# DifferentialPair.net
KiCad netlist of a schematic drawn in Altium Designer
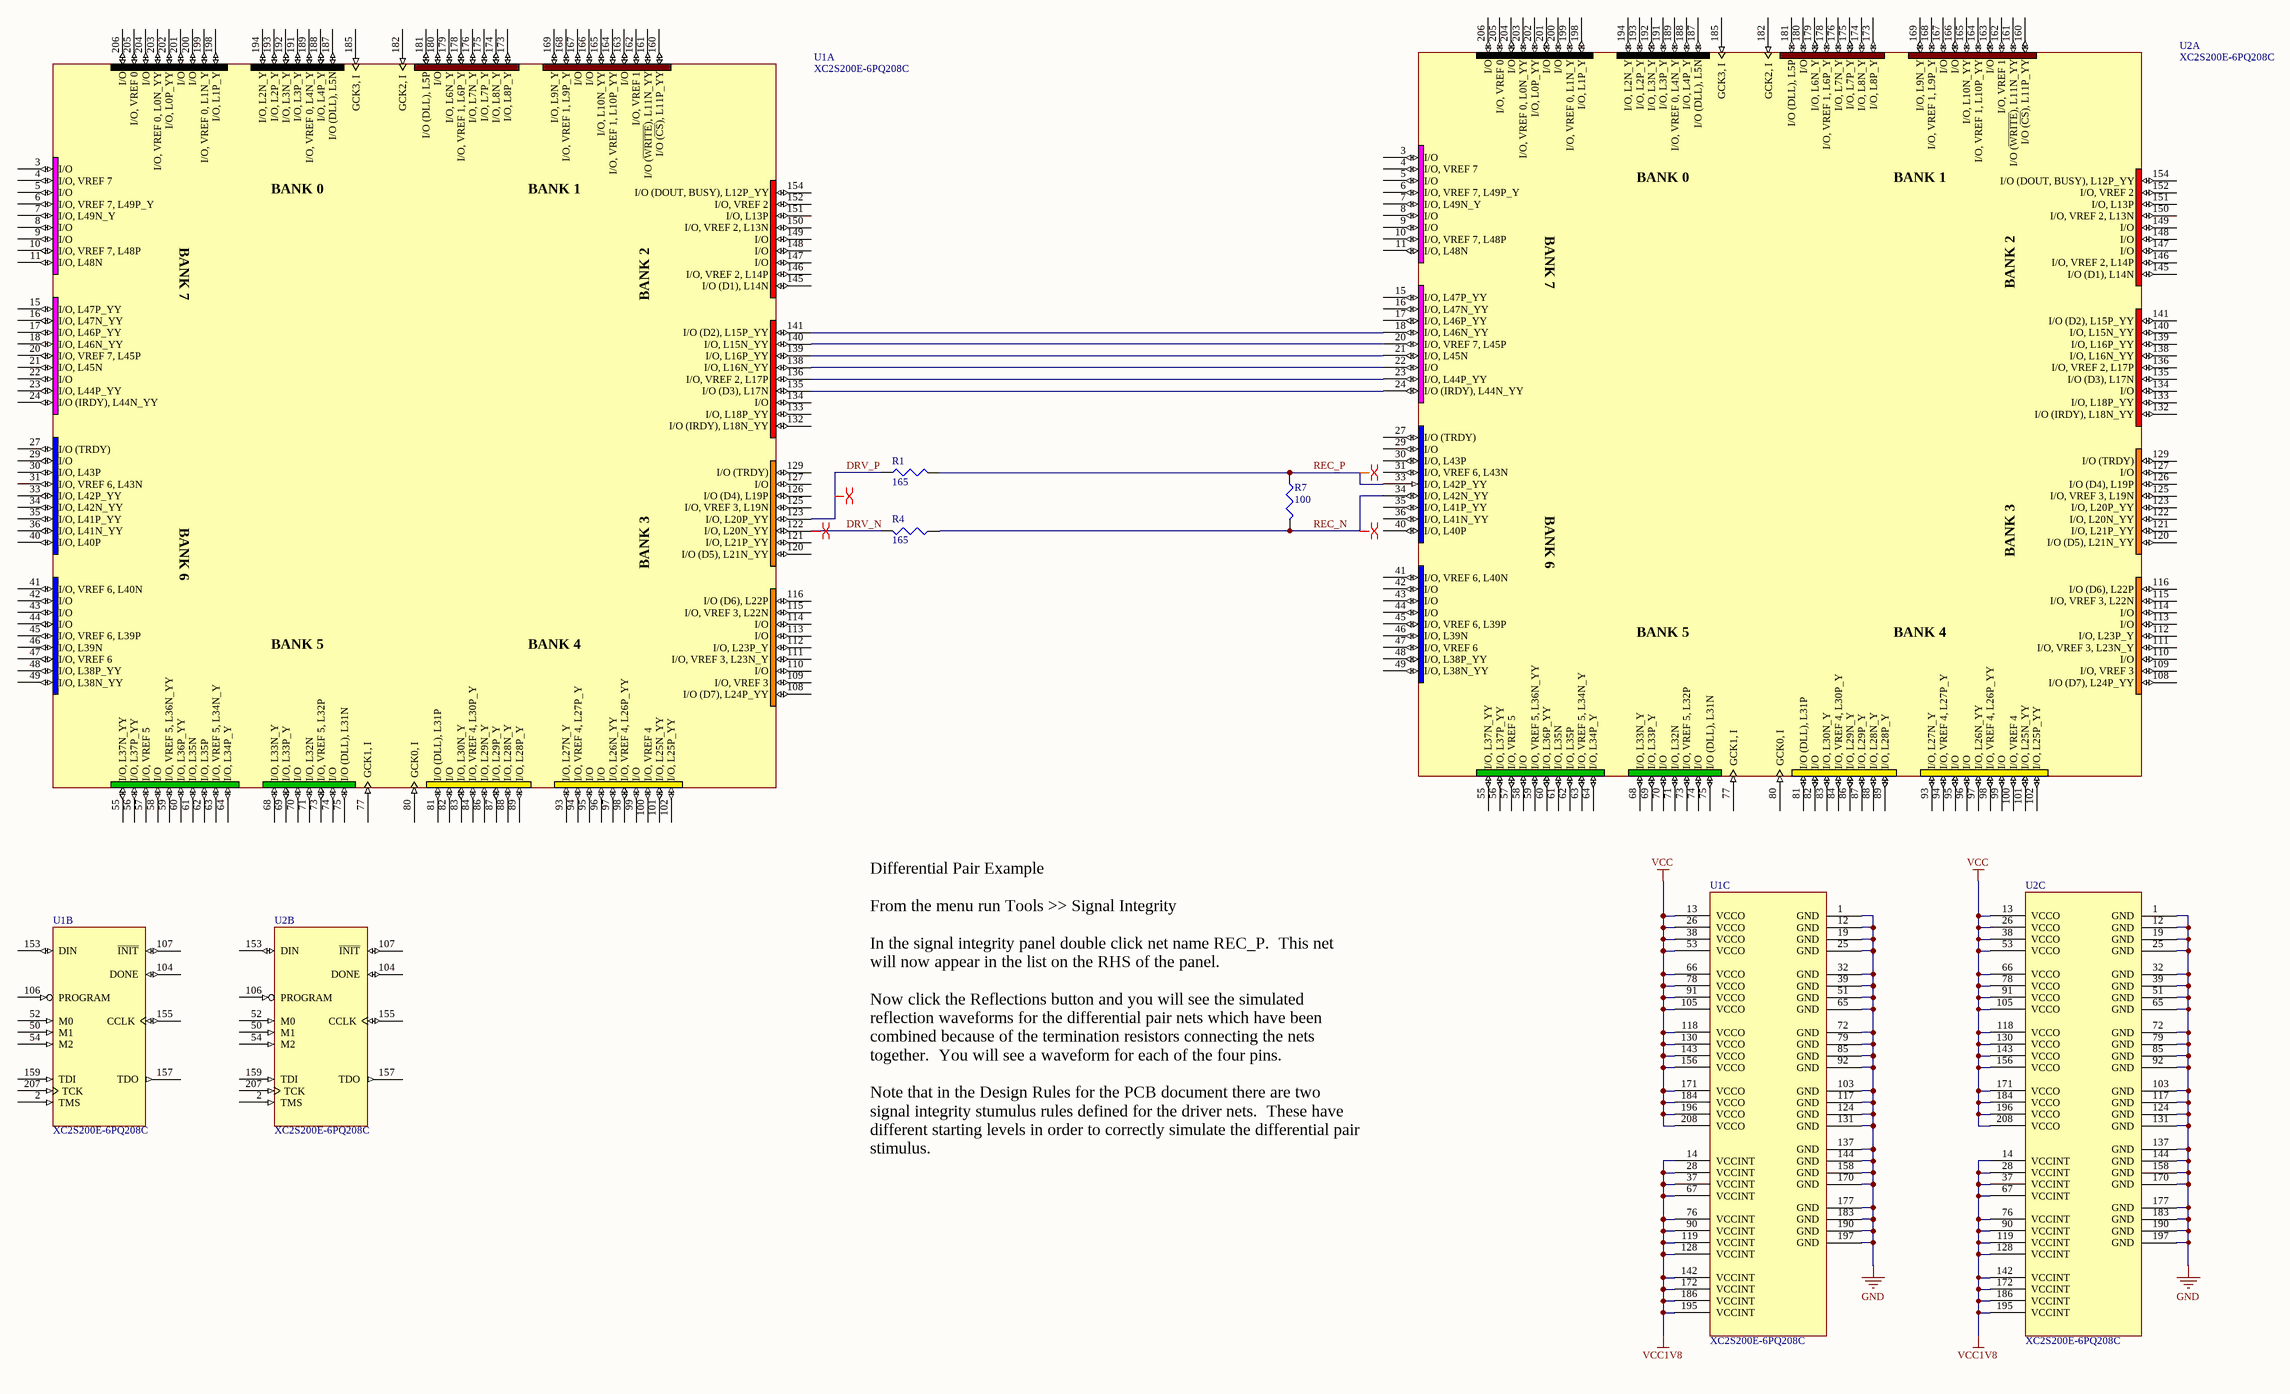
[diagram p0: DifferentialPair.SchDoc]

(export (version "E")
  (design (tool "Eeschema 10.0.6"))
  (components
    (comp (ref "R1")
      (value "165")
      (footprint "J1-0603")
      (description "Resistor")
      (fields (field (name "Comment") "Res3") (field (name "PUBLISHER") "Altium Limited"))
      (libsource (lib "Miscellaneous Devices") (part "Res3"))
    )
    (comp (ref "R4")
      (value "165")
      (footprint "J1-0603")
      (description "Resistor")
      (fields (field (name "Comment") "Res3") (field (name "PUBLISHER") "Altium Limited"))
      (libsource (lib "Miscellaneous Devices") (part "Res3"))
    )
    (comp (ref "R7")
      (value "100")
      (footprint "J1-0603")
      (description "Resistor")
      (fields (field (name "Comment") "Res3") (field (name "PUBLISHER") "Altium Limited"))
      (libsource (lib "Miscellaneous Devices") (part "Res3"))
    )
    (comp (ref "U1")
      (value "XC2S200E-6PQ208C")
      (footprint "PQ208")
      (description "Spartan-IIE 1.8V FPGA, 208-Pin PQFP, Standard Performance, Commercial Grade")
      (fields (field (name "PUBLISHER") "Altium Limited"))
      (libsource (lib "Xilinx Spartan-IIE") (part "XC2S200E-6PQ208C"))
    )
    (comp (ref "U2")
      (value "XC2S200E-6PQ208C")
      (footprint "PQ208")
      (description "Spartan-IIE 1.8V FPGA, 208-Pin PQFP, Standard Performance, Commercial Grade")
      (fields (field (name "PUBLISHER") "Altium Limited"))
      (libsource (lib "Xilinx Spartan-IIE") (part "XC2S200E-6PQ208C"))
    )
  )
  (nets
    (net (code "1") (name "/DRV_N") (class "Default")
      (node (ref "R4") (pin "2") (pinfunction "2_2") (pintype "passive"))
      (node (ref "U1") (pin "122") (pinfunction "I/O,_L20N_YY_122") (pintype "bidirectional"))
    )
    (net (code "2") (name "/DRV_P") (class "Default")
      (node (ref "R1") (pin "1") (pinfunction "1_1") (pintype "passive"))
      (node (ref "U1") (pin "123") (pinfunction "I/O,_L20P_YY_123") (pintype "bidirectional"))
    )
    (net (code "3") (name "/REC_N") (class "Default")
      (node (ref "R4") (pin "1") (pinfunction "1_1") (pintype "passive"))
      (node (ref "R7") (pin "2") (pinfunction "2_2") (pintype "passive"))
      (node (ref "U2") (pin "34") (pinfunction "I/O,_L42N_YY_34") (pintype "bidirectional"))
    )
    (net (code "4") (name "/REC_P") (class "Default")
      (node (ref "R1") (pin "2") (pinfunction "2_2") (pintype "passive"))
      (node (ref "R7") (pin "1") (pinfunction "1_1") (pintype "passive"))
      (node (ref "U2") (pin "33") (pinfunction "I/O,_L42P_YY_33") (pintype "input"))
    )
    (net (code "5") (name "GND") (class "Default")
      (node (ref "U1") (pin "1") (pinfunction "GND_1") (pintype "power_in"))
      (node (ref "U1") (pin "103") (pinfunction "GND_103") (pintype "power_in"))
      (node (ref "U1") (pin "117") (pinfunction "GND_117") (pintype "power_in"))
      (node (ref "U1") (pin "12") (pinfunction "GND_12") (pintype "power_in"))
      (node (ref "U1") (pin "124") (pinfunction "GND_124") (pintype "power_in"))
      (node (ref "U1") (pin "131") (pinfunction "GND_131") (pintype "power_in"))
      (node (ref "U1") (pin "137") (pinfunction "GND_137") (pintype "power_in"))
      (node (ref "U1") (pin "144") (pinfunction "GND_144") (pintype "power_in"))
      (node (ref "U1") (pin "158") (pinfunction "GND_158") (pintype "power_in"))
      (node (ref "U1") (pin "170") (pinfunction "GND_170") (pintype "power_in"))
      (node (ref "U1") (pin "177") (pinfunction "GND_177") (pintype "power_in"))
      (node (ref "U1") (pin "183") (pinfunction "GND_183") (pintype "power_in"))
      (node (ref "U1") (pin "19") (pinfunction "GND_19") (pintype "power_in"))
      (node (ref "U1") (pin "190") (pinfunction "GND_190") (pintype "power_in"))
      (node (ref "U1") (pin "197") (pinfunction "GND_197") (pintype "power_in"))
      (node (ref "U1") (pin "25") (pinfunction "GND_25") (pintype "power_in"))
      (node (ref "U1") (pin "32") (pinfunction "GND_32") (pintype "power_in"))
      (node (ref "U1") (pin "39") (pinfunction "GND_39") (pintype "power_in"))
      (node (ref "U1") (pin "51") (pinfunction "GND_51") (pintype "power_in"))
      (node (ref "U1") (pin "65") (pinfunction "GND_65") (pintype "power_in"))
      (node (ref "U1") (pin "72") (pinfunction "GND_72") (pintype "power_in"))
      (node (ref "U1") (pin "79") (pinfunction "GND_79") (pintype "power_in"))
      (node (ref "U1") (pin "85") (pinfunction "GND_85") (pintype "power_in"))
      (node (ref "U1") (pin "92") (pinfunction "GND_92") (pintype "power_in"))
      (node (ref "U2") (pin "1") (pinfunction "GND_1") (pintype "power_in"))
      (node (ref "U2") (pin "103") (pinfunction "GND_103") (pintype "power_in"))
      (node (ref "U2") (pin "117") (pinfunction "GND_117") (pintype "power_in"))
      (node (ref "U2") (pin "12") (pinfunction "GND_12") (pintype "power_in"))
      (node (ref "U2") (pin "124") (pinfunction "GND_124") (pintype "power_in"))
      (node (ref "U2") (pin "131") (pinfunction "GND_131") (pintype "power_in"))
      (node (ref "U2") (pin "137") (pinfunction "GND_137") (pintype "power_in"))
      (node (ref "U2") (pin "144") (pinfunction "GND_144") (pintype "power_in"))
      (node (ref "U2") (pin "158") (pinfunction "GND_158") (pintype "power_in"))
      (node (ref "U2") (pin "170") (pinfunction "GND_170") (pintype "power_in"))
      (node (ref "U2") (pin "177") (pinfunction "GND_177") (pintype "power_in"))
      (node (ref "U2") (pin "183") (pinfunction "GND_183") (pintype "power_in"))
      (node (ref "U2") (pin "19") (pinfunction "GND_19") (pintype "power_in"))
      (node (ref "U2") (pin "190") (pinfunction "GND_190") (pintype "power_in"))
      (node (ref "U2") (pin "197") (pinfunction "GND_197") (pintype "power_in"))
      (node (ref "U2") (pin "25") (pinfunction "GND_25") (pintype "power_in"))
      (node (ref "U2") (pin "32") (pinfunction "GND_32") (pintype "power_in"))
      (node (ref "U2") (pin "39") (pinfunction "GND_39") (pintype "power_in"))
      (node (ref "U2") (pin "51") (pinfunction "GND_51") (pintype "power_in"))
      (node (ref "U2") (pin "65") (pinfunction "GND_65") (pintype "power_in"))
      (node (ref "U2") (pin "72") (pinfunction "GND_72") (pintype "power_in"))
      (node (ref "U2") (pin "79") (pinfunction "GND_79") (pintype "power_in"))
      (node (ref "U2") (pin "85") (pinfunction "GND_85") (pintype "power_in"))
      (node (ref "U2") (pin "92") (pinfunction "GND_92") (pintype "power_in"))
    )
    (net (code "6") (name "Net-(U1A-I{slash}O,_L15N_YY)") (class "Default")
      (node (ref "U1") (pin "140") (pinfunction "I/O,_L15N_YY_140") (pintype "bidirectional"))
      (node (ref "U2") (pin "20") (pinfunction "I/O,_VREF_7,_L45P_20") (pintype "bidirectional"))
    )
    (net (code "7") (name "Net-(U1A-I{slash}O,_L16N_YY)") (class "Default")
      (node (ref "U1") (pin "138") (pinfunction "I/O,_L16N_YY_138") (pintype "bidirectional"))
      (node (ref "U2") (pin "22") (pinfunction "I/O_22") (pintype "bidirectional"))
    )
    (net (code "8") (name "Net-(U1A-I{slash}O,_L16P_YY)") (class "Default")
      (node (ref "U1") (pin "139") (pinfunction "I/O,_L16P_YY_139") (pintype "bidirectional"))
      (node (ref "U2") (pin "21") (pinfunction "I/O,_L45N_21") (pintype "bidirectional"))
    )
    (net (code "9") (name "Net-(U1A-I{slash}O,_VREF_2,_L17P)") (class "Default")
      (node (ref "U1") (pin "136") (pinfunction "I/O,_VREF_2,_L17P_136") (pintype "bidirectional"))
      (node (ref "U2") (pin "23") (pinfunction "I/O,_L44P_YY_23") (pintype "bidirectional"))
    )
    (net (code "10") (name "Net-(U1A-I{slash}O_(D2),_L15P_YY)") (class "Default")
      (node (ref "U1") (pin "141") (pinfunction "I/O_(D2),_L15P_YY_141") (pintype "bidirectional"))
      (node (ref "U2") (pin "18") (pinfunction "I/O,_L46N_YY_18") (pintype "bidirectional"))
    )
    (net (code "11") (name "Net-(U1A-I{slash}O_(D3),_L17N)") (class "Default")
      (node (ref "U1") (pin "135") (pinfunction "I/O_(D3),_L17N_135") (pintype "bidirectional"))
      (node (ref "U2") (pin "24") (pinfunction "I/O_(IRDY),_L44N_YY_24") (pintype "bidirectional"))
    )
    (net (code "12") (name "VCC") (class "Default")
      (node (ref "U1") (pin "105") (pinfunction "VCCO_105") (pintype "power_in"))
      (node (ref "U1") (pin "118") (pinfunction "VCCO_118") (pintype "power_in"))
      (node (ref "U1") (pin "13") (pinfunction "VCCO_13") (pintype "power_in"))
      (node (ref "U1") (pin "130") (pinfunction "VCCO_130") (pintype "power_in"))
      (node (ref "U1") (pin "143") (pinfunction "VCCO_143") (pintype "power_in"))
      (node (ref "U1") (pin "156") (pinfunction "VCCO_156") (pintype "power_in"))
      (node (ref "U1") (pin "171") (pinfunction "VCCO_171") (pintype "power_in"))
      (node (ref "U1") (pin "184") (pinfunction "VCCO_184") (pintype "power_in"))
      (node (ref "U1") (pin "196") (pinfunction "VCCO_196") (pintype "power_in"))
      (node (ref "U1") (pin "208") (pinfunction "VCCO_208") (pintype "power_in"))
      (node (ref "U1") (pin "26") (pinfunction "VCCO_26") (pintype "power_in"))
      (node (ref "U1") (pin "38") (pinfunction "VCCO_38") (pintype "power_in"))
      (node (ref "U1") (pin "53") (pinfunction "VCCO_53") (pintype "power_in"))
      (node (ref "U1") (pin "66") (pinfunction "VCCO_66") (pintype "power_in"))
      (node (ref "U1") (pin "78") (pinfunction "VCCO_78") (pintype "power_in"))
      (node (ref "U1") (pin "91") (pinfunction "VCCO_91") (pintype "power_in"))
      (node (ref "U2") (pin "105") (pinfunction "VCCO_105") (pintype "power_in"))
      (node (ref "U2") (pin "118") (pinfunction "VCCO_118") (pintype "power_in"))
      (node (ref "U2") (pin "13") (pinfunction "VCCO_13") (pintype "power_in"))
      (node (ref "U2") (pin "130") (pinfunction "VCCO_130") (pintype "power_in"))
      (node (ref "U2") (pin "143") (pinfunction "VCCO_143") (pintype "power_in"))
      (node (ref "U2") (pin "156") (pinfunction "VCCO_156") (pintype "power_in"))
      (node (ref "U2") (pin "171") (pinfunction "VCCO_171") (pintype "power_in"))
      (node (ref "U2") (pin "184") (pinfunction "VCCO_184") (pintype "power_in"))
      (node (ref "U2") (pin "196") (pinfunction "VCCO_196") (pintype "power_in"))
      (node (ref "U2") (pin "208") (pinfunction "VCCO_208") (pintype "power_in"))
      (node (ref "U2") (pin "26") (pinfunction "VCCO_26") (pintype "power_in"))
      (node (ref "U2") (pin "38") (pinfunction "VCCO_38") (pintype "power_in"))
      (node (ref "U2") (pin "53") (pinfunction "VCCO_53") (pintype "power_in"))
      (node (ref "U2") (pin "66") (pinfunction "VCCO_66") (pintype "power_in"))
      (node (ref "U2") (pin "78") (pinfunction "VCCO_78") (pintype "power_in"))
      (node (ref "U2") (pin "91") (pinfunction "VCCO_91") (pintype "power_in"))
    )
    (net (code "13") (name "VCC1V8") (class "Default")
      (node (ref "U1") (pin "119") (pinfunction "VCCINT_119") (pintype "power_in"))
      (node (ref "U1") (pin "128") (pinfunction "VCCINT_128") (pintype "power_in"))
      (node (ref "U1") (pin "14") (pinfunction "VCCINT_14") (pintype "power_in"))
      (node (ref "U1") (pin "142") (pinfunction "VCCINT_142") (pintype "power_in"))
      (node (ref "U1") (pin "172") (pinfunction "VCCINT_172") (pintype "power_in"))
      (node (ref "U1") (pin "186") (pinfunction "VCCINT_186") (pintype "power_in"))
      (node (ref "U1") (pin "195") (pinfunction "VCCINT_195") (pintype "power_in"))
      (node (ref "U1") (pin "28") (pinfunction "VCCINT_28") (pintype "power_in"))
      (node (ref "U1") (pin "37") (pinfunction "VCCINT_37") (pintype "power_in"))
      (node (ref "U1") (pin "67") (pinfunction "VCCINT_67") (pintype "power_in"))
      (node (ref "U1") (pin "76") (pinfunction "VCCINT_76") (pintype "power_in"))
      (node (ref "U1") (pin "90") (pinfunction "VCCINT_90") (pintype "power_in"))
      (node (ref "U2") (pin "119") (pinfunction "VCCINT_119") (pintype "power_in"))
      (node (ref "U2") (pin "128") (pinfunction "VCCINT_128") (pintype "power_in"))
      (node (ref "U2") (pin "14") (pinfunction "VCCINT_14") (pintype "power_in"))
      (node (ref "U2") (pin "142") (pinfunction "VCCINT_142") (pintype "power_in"))
      (node (ref "U2") (pin "172") (pinfunction "VCCINT_172") (pintype "power_in"))
      (node (ref "U2") (pin "186") (pinfunction "VCCINT_186") (pintype "power_in"))
      (node (ref "U2") (pin "195") (pinfunction "VCCINT_195") (pintype "power_in"))
      (node (ref "U2") (pin "28") (pinfunction "VCCINT_28") (pintype "power_in"))
      (node (ref "U2") (pin "37") (pinfunction "VCCINT_37") (pintype "power_in"))
      (node (ref "U2") (pin "67") (pinfunction "VCCINT_67") (pintype "power_in"))
      (node (ref "U2") (pin "76") (pinfunction "VCCINT_76") (pintype "power_in"))
      (node (ref "U2") (pin "90") (pinfunction "VCCINT_90") (pintype "power_in"))
    )
    (net (code "14") (name "unconnected-(U1A-GCK0,_I-Pad80)") (class "Default")
      (node (ref "U1") (pin "80") (pinfunction "GCK0,_I_80") (pintype "input"))
    )
    (net (code "15") (name "unconnected-(U1A-GCK1,_I-Pad77)") (class "Default")
      (node (ref "U1") (pin "77") (pinfunction "GCK1,_I_77") (pintype "input"))
    )
    (net (code "16") (name "unconnected-(U1A-GCK2,_I-Pad182)") (class "Default")
      (node (ref "U1") (pin "182") (pinfunction "GCK2,_I_182") (pintype "input"))
    )
    (net (code "17") (name "unconnected-(U1A-GCK3,_I-Pad185)") (class "Default")
      (node (ref "U1") (pin "185") (pinfunction "GCK3,_I_185") (pintype "input"))
    )
    (net (code "18") (name "unconnected-(U1A-I{slash}O,_L0P_YY-Pad202)") (class "Default")
      (node (ref "U1") (pin "202") (pinfunction "I/O,_L0P_YY_202") (pintype "bidirectional"))
    )
    (net (code "19") (name "unconnected-(U1A-I{slash}O,_L1P_Y-Pad198)") (class "Default")
      (node (ref "U1") (pin "198") (pinfunction "I/O,_L1P_Y_198") (pintype "bidirectional"))
    )
    (net (code "20") (name "unconnected-(U1A-I{slash}O,_L2N_Y-Pad194)") (class "Default")
      (node (ref "U1") (pin "194") (pinfunction "I/O,_L2N_Y_194") (pintype "bidirectional"))
    )
    (net (code "21") (name "unconnected-(U1A-I{slash}O,_L2P_Y-Pad193)") (class "Default")
      (node (ref "U1") (pin "193") (pinfunction "I/O,_L2P_Y_193") (pintype "bidirectional"))
    )
    (net (code "22") (name "unconnected-(U1A-I{slash}O,_L3N_Y-Pad192)") (class "Default")
      (node (ref "U1") (pin "192") (pinfunction "I/O,_L3N_Y_192") (pintype "bidirectional"))
    )
    (net (code "23") (name "unconnected-(U1A-I{slash}O,_L3P_Y-Pad191)") (class "Default")
      (node (ref "U1") (pin "191") (pinfunction "I/O,_L3P_Y_191") (pintype "bidirectional"))
    )
    (net (code "24") (name "unconnected-(U1A-I{slash}O,_L4P_Y-Pad188)") (class "Default")
      (node (ref "U1") (pin "188") (pinfunction "I/O,_L4P_Y_188") (pintype "bidirectional"))
    )
    (net (code "25") (name "unconnected-(U1A-I{slash}O,_L6N_Y-Pad179)") (class "Default")
      (node (ref "U1") (pin "179") (pinfunction "I/O,_L6N_Y_179") (pintype "bidirectional"))
    )
    (net (code "26") (name "unconnected-(U1A-I{slash}O,_L7N_Y-Pad176)") (class "Default")
      (node (ref "U1") (pin "176") (pinfunction "I/O,_L7N_Y_176") (pintype "bidirectional"))
    )
    (net (code "27") (name "unconnected-(U1A-I{slash}O,_L7P_Y-Pad175)") (class "Default")
      (node (ref "U1") (pin "175") (pinfunction "I/O,_L7P_Y_175") (pintype "bidirectional"))
    )
    (net (code "28") (name "unconnected-(U1A-I{slash}O,_L8N_Y-Pad174)") (class "Default")
      (node (ref "U1") (pin "174") (pinfunction "I/O,_L8N_Y_174") (pintype "bidirectional"))
    )
    (net (code "29") (name "unconnected-(U1A-I{slash}O,_L8P_Y-Pad173)") (class "Default")
      (node (ref "U1") (pin "173") (pinfunction "I/O,_L8P_Y_173") (pintype "bidirectional"))
    )
    (net (code "30") (name "unconnected-(U1A-I{slash}O,_L9N_Y-Pad169)") (class "Default")
      (node (ref "U1") (pin "169") (pinfunction "I/O,_L9N_Y_169") (pintype "bidirectional"))
    )
    (net (code "31") (name "unconnected-(U1A-I{slash}O,_L10N_YY-Pad165)") (class "Default")
      (node (ref "U1") (pin "165") (pinfunction "I/O,_L10N_YY_165") (pintype "bidirectional"))
    )
    (net (code "32") (name "unconnected-(U1A-I{slash}O,_L13P-Pad151)") (class "Default")
      (node (ref "U1") (pin "151") (pinfunction "I/O,_L13P_151") (pintype "bidirectional"))
    )
    (net (code "33") (name "unconnected-(U1A-I{slash}O,_L18P_YY-Pad133)") (class "Default")
      (node (ref "U1") (pin "133") (pinfunction "I/O,_L18P_YY_133") (pintype "bidirectional"))
    )
    (net (code "34") (name "unconnected-(U1A-I{slash}O,_L21P_YY-Pad121)") (class "Default")
      (node (ref "U1") (pin "121") (pinfunction "I/O,_L21P_YY_121") (pintype "bidirectional"))
    )
    (net (code "35") (name "unconnected-(U1A-I{slash}O,_L23P_Y-Pad112)") (class "Default")
      (node (ref "U1") (pin "112") (pinfunction "I/O,_L23P_Y_112") (pintype "bidirectional"))
    )
    (net (code "36") (name "unconnected-(U1A-I{slash}O,_L25N_YY-Pad101)") (class "Default")
      (node (ref "U1") (pin "101") (pinfunction "I/O,_L25N_YY_101") (pintype "bidirectional"))
    )
    (net (code "37") (name "unconnected-(U1A-I{slash}O,_L25P_YY-Pad102)") (class "Default")
      (node (ref "U1") (pin "102") (pinfunction "I/O,_L25P_YY_102") (pintype "bidirectional"))
    )
    (net (code "38") (name "unconnected-(U1A-I{slash}O,_L26N_YY-Pad97)") (class "Default")
      (node (ref "U1") (pin "97") (pinfunction "I/O,_L26N_YY_97") (pintype "bidirectional"))
    )
    (net (code "39") (name "unconnected-(U1A-I{slash}O,_L27N_Y-Pad93)") (class "Default")
      (node (ref "U1") (pin "93") (pinfunction "I/O,_L27N_Y_93") (pintype "bidirectional"))
    )
    (net (code "40") (name "unconnected-(U1A-I{slash}O,_L28N_Y-Pad88)") (class "Default")
      (node (ref "U1") (pin "88") (pinfunction "I/O,_L28N_Y_88") (pintype "bidirectional"))
    )
    (net (code "41") (name "unconnected-(U1A-I{slash}O,_L28P_Y-Pad89)") (class "Default")
      (node (ref "U1") (pin "89") (pinfunction "I/O,_L28P_Y_89") (pintype "bidirectional"))
    )
    (net (code "42") (name "unconnected-(U1A-I{slash}O,_L29N_Y-Pad86)") (class "Default")
      (node (ref "U1") (pin "86") (pinfunction "I/O,_L29N_Y_86") (pintype "bidirectional"))
    )
    (net (code "43") (name "unconnected-(U1A-I{slash}O,_L29P_Y-Pad87)") (class "Default")
      (node (ref "U1") (pin "87") (pinfunction "I/O,_L29P_Y_87") (pintype "bidirectional"))
    )
    (net (code "44") (name "unconnected-(U1A-I{slash}O,_L30N_Y-Pad83)") (class "Default")
      (node (ref "U1") (pin "83") (pinfunction "I/O,_L30N_Y_83") (pintype "bidirectional"))
    )
    (net (code "45") (name "unconnected-(U1A-I{slash}O,_L32N-Pad71)") (class "Default")
      (node (ref "U1") (pin "71") (pinfunction "I/O,_L32N_71") (pintype "bidirectional"))
    )
    (net (code "46") (name "unconnected-(U1A-I{slash}O,_L33N_Y-Pad68)") (class "Default")
      (node (ref "U1") (pin "68") (pinfunction "I/O,_L33N_Y_68") (pintype "bidirectional"))
    )
    (net (code "47") (name "unconnected-(U1A-I{slash}O,_L33P_Y-Pad69)") (class "Default")
      (node (ref "U1") (pin "69") (pinfunction "I/O,_L33P_Y_69") (pintype "bidirectional"))
    )
    (net (code "48") (name "unconnected-(U1A-I{slash}O,_L34P_Y-Pad64)") (class "Default")
      (node (ref "U1") (pin "64") (pinfunction "I/O,_L34P_Y_64") (pintype "bidirectional"))
    )
    (net (code "49") (name "unconnected-(U1A-I{slash}O,_L35N-Pad61)") (class "Default")
      (node (ref "U1") (pin "61") (pinfunction "I/O,_L35N_61") (pintype "bidirectional"))
    )
    (net (code "50") (name "unconnected-(U1A-I{slash}O,_L35P-Pad62)") (class "Default")
      (node (ref "U1") (pin "62") (pinfunction "I/O,_L35P_62") (pintype "bidirectional"))
    )
    (net (code "51") (name "unconnected-(U1A-I{slash}O,_L36P_YY-Pad60)") (class "Default")
      (node (ref "U1") (pin "60") (pinfunction "I/O,_L36P_YY_60") (pintype "bidirectional"))
    )
    (net (code "52") (name "unconnected-(U1A-I{slash}O,_L37N_YY-Pad55)") (class "Default")
      (node (ref "U1") (pin "55") (pinfunction "I/O,_L37N_YY_55") (pintype "bidirectional"))
    )
    (net (code "53") (name "unconnected-(U1A-I{slash}O,_L37P_YY-Pad56)") (class "Default")
      (node (ref "U1") (pin "56") (pinfunction "I/O,_L37P_YY_56") (pintype "bidirectional"))
    )
    (net (code "54") (name "unconnected-(U1A-I{slash}O,_L38N_YY-Pad49)") (class "Default")
      (node (ref "U1") (pin "49") (pinfunction "I/O,_L38N_YY_49") (pintype "bidirectional"))
    )
    (net (code "55") (name "unconnected-(U1A-I{slash}O,_L38P_YY-Pad48)") (class "Default")
      (node (ref "U1") (pin "48") (pinfunction "I/O,_L38P_YY_48") (pintype "bidirectional"))
    )
    (net (code "56") (name "unconnected-(U1A-I{slash}O,_L39N-Pad46)") (class "Default")
      (node (ref "U1") (pin "46") (pinfunction "I/O,_L39N_46") (pintype "bidirectional"))
    )
    (net (code "57") (name "unconnected-(U1A-I{slash}O,_L40P-Pad40)") (class "Default")
      (node (ref "U1") (pin "40") (pinfunction "I/O,_L40P_40") (pintype "bidirectional"))
    )
    (net (code "58") (name "unconnected-(U1A-I{slash}O,_L41N_YY-Pad36)") (class "Default")
      (node (ref "U1") (pin "36") (pinfunction "I/O,_L41N_YY_36") (pintype "bidirectional"))
    )
    (net (code "59") (name "unconnected-(U1A-I{slash}O,_L41P_YY-Pad35)") (class "Default")
      (node (ref "U1") (pin "35") (pinfunction "I/O,_L41P_YY_35") (pintype "bidirectional"))
    )
    (net (code "60") (name "unconnected-(U1A-I{slash}O,_L42N_YY-Pad34)") (class "Default")
      (node (ref "U1") (pin "34") (pinfunction "I/O,_L42N_YY_34") (pintype "bidirectional"))
    )
    (net (code "61") (name "unconnected-(U1A-I{slash}O,_L42P_YY-Pad33)") (class "Default")
      (node (ref "U1") (pin "33") (pinfunction "I/O,_L42P_YY_33") (pintype "input"))
    )
    (net (code "62") (name "unconnected-(U1A-I{slash}O,_L43P-Pad30)") (class "Default")
      (node (ref "U1") (pin "30") (pinfunction "I/O,_L43P_30") (pintype "bidirectional"))
    )
    (net (code "63") (name "unconnected-(U1A-I{slash}O,_L44P_YY-Pad23)") (class "Default")
      (node (ref "U1") (pin "23") (pinfunction "I/O,_L44P_YY_23") (pintype "bidirectional"))
    )
    (net (code "64") (name "unconnected-(U1A-I{slash}O,_L45N-Pad21)") (class "Default")
      (node (ref "U1") (pin "21") (pinfunction "I/O,_L45N_21") (pintype "bidirectional"))
    )
    (net (code "65") (name "unconnected-(U1A-I{slash}O,_L46N_YY-Pad18)") (class "Default")
      (node (ref "U1") (pin "18") (pinfunction "I/O,_L46N_YY_18") (pintype "bidirectional"))
    )
    (net (code "66") (name "unconnected-(U1A-I{slash}O,_L46P_YY-Pad17)") (class "Default")
      (node (ref "U1") (pin "17") (pinfunction "I/O,_L46P_YY_17") (pintype "bidirectional"))
    )
    (net (code "67") (name "unconnected-(U1A-I{slash}O,_L47N_YY-Pad16)") (class "Default")
      (node (ref "U1") (pin "16") (pinfunction "I/O,_L47N_YY_16") (pintype "bidirectional"))
    )
    (net (code "68") (name "unconnected-(U1A-I{slash}O,_L47P_YY-Pad15)") (class "Default")
      (node (ref "U1") (pin "15") (pinfunction "I/O,_L47P_YY_15") (pintype "bidirectional"))
    )
    (net (code "69") (name "unconnected-(U1A-I{slash}O,_L48N-Pad11)") (class "Default")
      (node (ref "U1") (pin "11") (pinfunction "I/O,_L48N_11") (pintype "bidirectional"))
    )
    (net (code "70") (name "unconnected-(U1A-I{slash}O,_L49N_Y-Pad7)") (class "Default")
      (node (ref "U1") (pin "7") (pinfunction "I/O,_L49N_Y_7") (pintype "bidirectional"))
    )
    (net (code "71") (name "unconnected-(U1A-I{slash}O,_VREF_0,_L0N_YY-Pad203)") (class "Default")
      (node (ref "U1") (pin "203") (pinfunction "I/O,_VREF_0,_L0N_YY_203") (pintype "bidirectional"))
    )
    (net (code "72") (name "unconnected-(U1A-I{slash}O,_VREF_0,_L1N_Y-Pad199)") (class "Default")
      (node (ref "U1") (pin "199") (pinfunction "I/O,_VREF_0,_L1N_Y_199") (pintype "bidirectional"))
    )
    (net (code "73") (name "unconnected-(U1A-I{slash}O,_VREF_0,_L4N_Y-Pad189)") (class "Default")
      (node (ref "U1") (pin "189") (pinfunction "I/O,_VREF_0,_L4N_Y_189") (pintype "bidirectional"))
    )
    (net (code "74") (name "unconnected-(U1A-I{slash}O,_VREF_0-Pad205)") (class "Default")
      (node (ref "U1") (pin "205") (pinfunction "I/O,_VREF_0_205") (pintype "bidirectional"))
    )
    (net (code "75") (name "unconnected-(U1A-I{slash}O,_VREF_1,_L6P_Y-Pad178)") (class "Default")
      (node (ref "U1") (pin "178") (pinfunction "I/O,_VREF_1,_L6P_Y_178") (pintype "bidirectional"))
    )
    (net (code "76") (name "unconnected-(U1A-I{slash}O,_VREF_1,_L9P_Y-Pad168)") (class "Default")
      (node (ref "U1") (pin "168") (pinfunction "I/O,_VREF_1,_L9P_Y_168") (pintype "bidirectional"))
    )
    (net (code "77") (name "unconnected-(U1A-I{slash}O,_VREF_1,_L10P_YY-Pad164)") (class "Default")
      (node (ref "U1") (pin "164") (pinfunction "I/O,_VREF_1,_L10P_YY_164") (pintype "bidirectional"))
    )
    (net (code "78") (name "unconnected-(U1A-I{slash}O,_VREF_1-Pad162)") (class "Default")
      (node (ref "U1") (pin "162") (pinfunction "I/O,_VREF_1_162") (pintype "bidirectional"))
    )
    (net (code "79") (name "unconnected-(U1A-I{slash}O,_VREF_2,_L13N-Pad150)") (class "Default")
      (node (ref "U1") (pin "150") (pinfunction "I/O,_VREF_2,_L13N_150") (pintype "bidirectional"))
    )
    (net (code "80") (name "unconnected-(U1A-I{slash}O,_VREF_2,_L14P-Pad146)") (class "Default")
      (node (ref "U1") (pin "146") (pinfunction "I/O,_VREF_2,_L14P_146") (pintype "bidirectional"))
    )
    (net (code "81") (name "unconnected-(U1A-I{slash}O,_VREF_2-Pad152)") (class "Default")
      (node (ref "U1") (pin "152") (pinfunction "I/O,_VREF_2_152") (pintype "bidirectional"))
    )
    (net (code "82") (name "unconnected-(U1A-I{slash}O,_VREF_3,_L19N-Pad125)") (class "Default")
      (node (ref "U1") (pin "125") (pinfunction "I/O,_VREF_3,_L19N_125") (pintype "bidirectional"))
    )
    (net (code "83") (name "unconnected-(U1A-I{slash}O,_VREF_3,_L22N-Pad115)") (class "Default")
      (node (ref "U1") (pin "115") (pinfunction "I/O,_VREF_3,_L22N_115") (pintype "bidirectional"))
    )
    (net (code "84") (name "unconnected-(U1A-I{slash}O,_VREF_3,_L23N_Y-Pad111)") (class "Default")
      (node (ref "U1") (pin "111") (pinfunction "I/O,_VREF_3,_L23N_Y_111") (pintype "bidirectional"))
    )
    (net (code "85") (name "unconnected-(U1A-I{slash}O,_VREF_3-Pad109)") (class "Default")
      (node (ref "U1") (pin "109") (pinfunction "I/O,_VREF_3_109") (pintype "bidirectional"))
    )
    (net (code "86") (name "unconnected-(U1A-I{slash}O,_VREF_4,_L26P_YY-Pad98)") (class "Default")
      (node (ref "U1") (pin "98") (pinfunction "I/O,_VREF_4,_L26P_YY_98") (pintype "bidirectional"))
    )
    (net (code "87") (name "unconnected-(U1A-I{slash}O,_VREF_4,_L27P_Y-Pad94)") (class "Default")
      (node (ref "U1") (pin "94") (pinfunction "I/O,_VREF_4,_L27P_Y_94") (pintype "bidirectional"))
    )
    (net (code "88") (name "unconnected-(U1A-I{slash}O,_VREF_4,_L30P_Y-Pad84)") (class "Default")
      (node (ref "U1") (pin "84") (pinfunction "I/O,_VREF_4,_L30P_Y_84") (pintype "bidirectional"))
    )
    (net (code "89") (name "unconnected-(U1A-I{slash}O,_VREF_4-Pad100)") (class "Default")
      (node (ref "U1") (pin "100") (pinfunction "I/O,_VREF_4_100") (pintype "bidirectional"))
    )
    (net (code "90") (name "unconnected-(U1A-I{slash}O,_VREF_5,_L32P-Pad73)") (class "Default")
      (node (ref "U1") (pin "73") (pinfunction "I/O,_VREF_5,_L32P_73") (pintype "bidirectional"))
    )
    (net (code "91") (name "unconnected-(U1A-I{slash}O,_VREF_5,_L34N_Y-Pad63)") (class "Default")
      (node (ref "U1") (pin "63") (pinfunction "I/O,_VREF_5,_L34N_Y_63") (pintype "bidirectional"))
    )
    (net (code "92") (name "unconnected-(U1A-I{slash}O,_VREF_5,_L36N_YY-Pad59)") (class "Default")
      (node (ref "U1") (pin "59") (pinfunction "I/O,_VREF_5,_L36N_YY_59") (pintype "bidirectional"))
    )
    (net (code "93") (name "unconnected-(U1A-I{slash}O,_VREF_5-Pad57)") (class "Default")
      (node (ref "U1") (pin "57") (pinfunction "I/O,_VREF_5_57") (pintype "bidirectional"))
    )
    (net (code "94") (name "unconnected-(U1A-I{slash}O,_VREF_6,_L39P-Pad45)") (class "Default")
      (node (ref "U1") (pin "45") (pinfunction "I/O,_VREF_6,_L39P_45") (pintype "bidirectional"))
    )
    (net (code "95") (name "unconnected-(U1A-I{slash}O,_VREF_6,_L40N-Pad41)") (class "Default")
      (node (ref "U1") (pin "41") (pinfunction "I/O,_VREF_6,_L40N_41") (pintype "bidirectional"))
    )
    (net (code "96") (name "unconnected-(U1A-I{slash}O,_VREF_6,_L43N-Pad31)") (class "Default")
      (node (ref "U1") (pin "31") (pinfunction "I/O,_VREF_6,_L43N_31") (pintype "bidirectional"))
    )
    (net (code "97") (name "unconnected-(U1A-I{slash}O,_VREF_6-Pad47)") (class "Default")
      (node (ref "U1") (pin "47") (pinfunction "I/O,_VREF_6_47") (pintype "bidirectional"))
    )
    (net (code "98") (name "unconnected-(U1A-I{slash}O,_VREF_7,_L45P-Pad20)") (class "Default")
      (node (ref "U1") (pin "20") (pinfunction "I/O,_VREF_7,_L45P_20") (pintype "bidirectional"))
    )
    (net (code "99") (name "unconnected-(U1A-I{slash}O,_VREF_7,_L48P-Pad10)") (class "Default")
      (node (ref "U1") (pin "10") (pinfunction "I/O,_VREF_7,_L48P_10") (pintype "bidirectional"))
    )
    (net (code "100") (name "unconnected-(U1A-I{slash}O,_VREF_7,_L49P_Y-Pad6)") (class "Default")
      (node (ref "U1") (pin "6") (pinfunction "I/O,_VREF_7,_L49P_Y_6") (pintype "bidirectional"))
    )
    (net (code "101") (name "unconnected-(U1A-I{slash}O,_VREF_7-Pad4)") (class "Default")
      (node (ref "U1") (pin "4") (pinfunction "I/O,_VREF_7_4") (pintype "bidirectional"))
    )
    (net (code "102") (name "unconnected-(U1A-I{slash}O-Pad3)") (class "Default")
      (node (ref "U1") (pin "3") (pinfunction "I/O_3") (pintype "bidirectional"))
    )
    (net (code "103") (name "unconnected-(U1A-I{slash}O-Pad5)") (class "Default")
      (node (ref "U1") (pin "5") (pinfunction "I/O_5") (pintype "bidirectional"))
    )
    (net (code "104") (name "unconnected-(U1A-I{slash}O-Pad8)") (class "Default")
      (node (ref "U1") (pin "8") (pinfunction "I/O_8") (pintype "bidirectional"))
    )
    (net (code "105") (name "unconnected-(U1A-I{slash}O-Pad9)") (class "Default")
      (node (ref "U1") (pin "9") (pinfunction "I/O_9") (pintype "bidirectional"))
    )
    (net (code "106") (name "unconnected-(U1A-I{slash}O-Pad22)") (class "Default")
      (node (ref "U1") (pin "22") (pinfunction "I/O_22") (pintype "bidirectional"))
    )
    (net (code "107") (name "unconnected-(U1A-I{slash}O-Pad29)") (class "Default")
      (node (ref "U1") (pin "29") (pinfunction "I/O_29") (pintype "bidirectional"))
    )
    (net (code "108") (name "unconnected-(U1A-I{slash}O-Pad42)") (class "Default")
      (node (ref "U1") (pin "42") (pinfunction "I/O_42") (pintype "bidirectional"))
    )
    (net (code "109") (name "unconnected-(U1A-I{slash}O-Pad43)") (class "Default")
      (node (ref "U1") (pin "43") (pinfunction "I/O_43") (pintype "bidirectional"))
    )
    (net (code "110") (name "unconnected-(U1A-I{slash}O-Pad44)") (class "Default")
      (node (ref "U1") (pin "44") (pinfunction "I/O_44") (pintype "bidirectional"))
    )
    (net (code "111") (name "unconnected-(U1A-I{slash}O-Pad58)") (class "Default")
      (node (ref "U1") (pin "58") (pinfunction "I/O_58") (pintype "bidirectional"))
    )
    (net (code "112") (name "unconnected-(U1A-I{slash}O-Pad70)") (class "Default")
      (node (ref "U1") (pin "70") (pinfunction "I/O_70") (pintype "bidirectional"))
    )
    (net (code "113") (name "unconnected-(U1A-I{slash}O-Pad74)") (class "Default")
      (node (ref "U1") (pin "74") (pinfunction "I/O_74") (pintype "bidirectional"))
    )
    (net (code "114") (name "unconnected-(U1A-I{slash}O-Pad82)") (class "Default")
      (node (ref "U1") (pin "82") (pinfunction "I/O_82") (pintype "bidirectional"))
    )
    (net (code "115") (name "unconnected-(U1A-I{slash}O-Pad95)") (class "Default")
      (node (ref "U1") (pin "95") (pinfunction "I/O_95") (pintype "bidirectional"))
    )
    (net (code "116") (name "unconnected-(U1A-I{slash}O-Pad96)") (class "Default")
      (node (ref "U1") (pin "96") (pinfunction "I/O_96") (pintype "bidirectional"))
    )
    (net (code "117") (name "unconnected-(U1A-I{slash}O-Pad99)") (class "Default")
      (node (ref "U1") (pin "99") (pinfunction "I/O_99") (pintype "bidirectional"))
    )
    (net (code "118") (name "unconnected-(U1A-I{slash}O-Pad110)") (class "Default")
      (node (ref "U1") (pin "110") (pinfunction "I/O_110") (pintype "bidirectional"))
    )
    (net (code "119") (name "unconnected-(U1A-I{slash}O-Pad113)") (class "Default")
      (node (ref "U1") (pin "113") (pinfunction "I/O_113") (pintype "bidirectional"))
    )
    (net (code "120") (name "unconnected-(U1A-I{slash}O-Pad114)") (class "Default")
      (node (ref "U1") (pin "114") (pinfunction "I/O_114") (pintype "bidirectional"))
    )
    (net (code "121") (name "unconnected-(U1A-I{slash}O-Pad127)") (class "Default")
      (node (ref "U1") (pin "127") (pinfunction "I/O_127") (pintype "bidirectional"))
    )
    (net (code "122") (name "unconnected-(U1A-I{slash}O-Pad134)") (class "Default")
      (node (ref "U1") (pin "134") (pinfunction "I/O_134") (pintype "bidirectional"))
    )
    (net (code "123") (name "unconnected-(U1A-I{slash}O-Pad147)") (class "Default")
      (node (ref "U1") (pin "147") (pinfunction "I/O_147") (pintype "bidirectional"))
    )
    (net (code "124") (name "unconnected-(U1A-I{slash}O-Pad148)") (class "Default")
      (node (ref "U1") (pin "148") (pinfunction "I/O_148") (pintype "bidirectional"))
    )
    (net (code "125") (name "unconnected-(U1A-I{slash}O-Pad149)") (class "Default")
      (node (ref "U1") (pin "149") (pinfunction "I/O_149") (pintype "bidirectional"))
    )
    (net (code "126") (name "unconnected-(U1A-I{slash}O-Pad163)") (class "Default")
      (node (ref "U1") (pin "163") (pinfunction "I/O_163") (pintype "bidirectional"))
    )
    (net (code "127") (name "unconnected-(U1A-I{slash}O-Pad166)") (class "Default")
      (node (ref "U1") (pin "166") (pinfunction "I/O_166") (pintype "bidirectional"))
    )
    (net (code "128") (name "unconnected-(U1A-I{slash}O-Pad167)") (class "Default")
      (node (ref "U1") (pin "167") (pinfunction "I/O_167") (pintype "bidirectional"))
    )
    (net (code "129") (name "unconnected-(U1A-I{slash}O-Pad180)") (class "Default")
      (node (ref "U1") (pin "180") (pinfunction "I/O_180") (pintype "bidirectional"))
    )
    (net (code "130") (name "unconnected-(U1A-I{slash}O-Pad200)") (class "Default")
      (node (ref "U1") (pin "200") (pinfunction "I/O_200") (pintype "bidirectional"))
    )
    (net (code "131") (name "unconnected-(U1A-I{slash}O-Pad201)") (class "Default")
      (node (ref "U1") (pin "201") (pinfunction "I/O_201") (pintype "bidirectional"))
    )
    (net (code "132") (name "unconnected-(U1A-I{slash}O-Pad204)") (class "Default")
      (node (ref "U1") (pin "204") (pinfunction "I/O_204") (pintype "bidirectional"))
    )
    (net (code "133") (name "unconnected-(U1A-I{slash}O-Pad206)") (class "Default")
      (node (ref "U1") (pin "206") (pinfunction "I/O_206") (pintype "bidirectional"))
    )
    (net (code "134") (name "unconnected-(U1A-I{slash}O_(D1),_L14N-Pad145)") (class "Default")
      (node (ref "U1") (pin "145") (pinfunction "I/O_(D1),_L14N_145") (pintype "bidirectional"))
    )
    (net (code "135") (name "unconnected-(U1A-I{slash}O_(D4),_L19P-Pad126)") (class "Default")
      (node (ref "U1") (pin "126") (pinfunction "I/O_(D4),_L19P_126") (pintype "bidirectional"))
    )
    (net (code "136") (name "unconnected-(U1A-I{slash}O_(D5),_L21N_YY-Pad120)") (class "Default")
      (node (ref "U1") (pin "120") (pinfunction "I/O_(D5),_L21N_YY_120") (pintype "bidirectional"))
    )
    (net (code "137") (name "unconnected-(U1A-I{slash}O_(D6),_L22P-Pad116)") (class "Default")
      (node (ref "U1") (pin "116") (pinfunction "I/O_(D6),_L22P_116") (pintype "bidirectional"))
    )
    (net (code "138") (name "unconnected-(U1A-I{slash}O_(D7),_L24P_YY-Pad108)") (class "Default")
      (node (ref "U1") (pin "108") (pinfunction "I/O_(D7),_L24P_YY_108") (pintype "bidirectional"))
    )
    (net (code "139") (name "unconnected-(U1A-I{slash}O_(DLL),_L5N-Pad187)") (class "Default")
      (node (ref "U1") (pin "187") (pinfunction "I/O_(DLL),_L5N_187") (pintype "bidirectional"))
    )
    (net (code "140") (name "unconnected-(U1A-I{slash}O_(DLL),_L5P-Pad181)") (class "Default")
      (node (ref "U1") (pin "181") (pinfunction "I/O_(DLL),_L5P_181") (pintype "bidirectional"))
    )
    (net (code "141") (name "unconnected-(U1A-I{slash}O_(DLL),_L31N-Pad75)") (class "Default")
      (node (ref "U1") (pin "75") (pinfunction "I/O_(DLL),_L31N_75") (pintype "bidirectional"))
    )
    (net (code "142") (name "unconnected-(U1A-I{slash}O_(DLL),_L31P-Pad81)") (class "Default")
      (node (ref "U1") (pin "81") (pinfunction "I/O_(DLL),_L31P_81") (pintype "bidirectional"))
    )
    (net (code "143") (name "unconnected-(U1A-I{slash}O_(DOUT,_BUSY),_L12P_YY-Pad154)") (class "Default")
      (node (ref "U1") (pin "154") (pinfunction "I/O_(DOUT,_BUSY),_L12P_YY_154") (pintype "bidirectional"))
    )
    (net (code "144") (name "unconnected-(U1A-I{slash}O_(IRDY),_L18N_YY-Pad132)") (class "Default")
      (node (ref "U1") (pin "132") (pinfunction "I/O_(IRDY),_L18N_YY_132") (pintype "bidirectional"))
    )
    (net (code "145") (name "unconnected-(U1A-I{slash}O_(IRDY),_L44N_YY-Pad24)") (class "Default")
      (node (ref "U1") (pin "24") (pinfunction "I/O_(IRDY),_L44N_YY_24") (pintype "bidirectional"))
    )
    (net (code "146") (name "unconnected-(U1A-I{slash}O_(TRDY)-Pad27)") (class "Default")
      (node (ref "U1") (pin "27") (pinfunction "I/O_(TRDY)_27") (pintype "bidirectional"))
    )
    (net (code "147") (name "unconnected-(U1A-I{slash}O_(TRDY)-Pad129)") (class "Default")
      (node (ref "U1") (pin "129") (pinfunction "I/O_(TRDY)_129") (pintype "bidirectional"))
    )
    (net (code "148") (name "unconnected-(U1A-I{slash}O_(~{CS}),_L11P_YY-Pad160)") (class "Default")
      (node (ref "U1") (pin "160") (pinfunction "I/O_(~{CS}),_L11P_YY_160") (pintype "bidirectional"))
    )
    (net (code "149") (name "unconnected-(U1A-I{slash}O_(~{WRITE}),_L11N_YY-Pad161)") (class "Default")
      (node (ref "U1") (pin "161") (pinfunction "I/O_(~{WRITE}),_L11N_YY_161") (pintype "bidirectional"))
    )
    (net (code "150") (name "unconnected-(U1B-CCLK-Pad155)") (class "Default")
      (node (ref "U1") (pin "155") (pinfunction "CCLK_155") (pintype "bidirectional"))
    )
    (net (code "151") (name "unconnected-(U1B-DIN-Pad153)") (class "Default")
      (node (ref "U1") (pin "153") (pinfunction "DIN_153") (pintype "bidirectional"))
    )
    (net (code "152") (name "unconnected-(U1B-DONE-Pad104)") (class "Default")
      (node (ref "U1") (pin "104") (pinfunction "DONE_104") (pintype "bidirectional"))
    )
    (net (code "153") (name "unconnected-(U1B-M0-Pad52)") (class "Default")
      (node (ref "U1") (pin "52") (pinfunction "M0_52") (pintype "input"))
    )
    (net (code "154") (name "unconnected-(U1B-M1-Pad50)") (class "Default")
      (node (ref "U1") (pin "50") (pinfunction "M1_50") (pintype "input"))
    )
    (net (code "155") (name "unconnected-(U1B-M2-Pad54)") (class "Default")
      (node (ref "U1") (pin "54") (pinfunction "M2_54") (pintype "input"))
    )
    (net (code "156") (name "unconnected-(U1B-PROGRAM-Pad106)") (class "Default")
      (node (ref "U1") (pin "106") (pinfunction "PROGRAM_106") (pintype "input"))
    )
    (net (code "157") (name "unconnected-(U1B-TCK-Pad207)") (class "Default")
      (node (ref "U1") (pin "207") (pinfunction "TCK_207") (pintype "input"))
    )
    (net (code "158") (name "unconnected-(U1B-TDI-Pad159)") (class "Default")
      (node (ref "U1") (pin "159") (pinfunction "TDI_159") (pintype "input"))
    )
    (net (code "159") (name "unconnected-(U1B-TDO-Pad157)") (class "Default")
      (node (ref "U1") (pin "157") (pinfunction "TDO_157") (pintype "output"))
    )
    (net (code "160") (name "unconnected-(U1B-TMS-Pad2)") (class "Default")
      (node (ref "U1") (pin "2") (pinfunction "TMS_2") (pintype "input"))
    )
    (net (code "161") (name "unconnected-(U1B-~{INIT}-Pad107)") (class "Default")
      (node (ref "U1") (pin "107") (pinfunction "~{INIT}_107") (pintype "bidirectional"))
    )
    (net (code "162") (name "unconnected-(U2A-GCK0,_I-Pad80)") (class "Default")
      (node (ref "U2") (pin "80") (pinfunction "GCK0,_I_80") (pintype "input"))
    )
    (net (code "163") (name "unconnected-(U2A-GCK1,_I-Pad77)") (class "Default")
      (node (ref "U2") (pin "77") (pinfunction "GCK1,_I_77") (pintype "input"))
    )
    (net (code "164") (name "unconnected-(U2A-GCK2,_I-Pad182)") (class "Default")
      (node (ref "U2") (pin "182") (pinfunction "GCK2,_I_182") (pintype "input"))
    )
    (net (code "165") (name "unconnected-(U2A-GCK3,_I-Pad185)") (class "Default")
      (node (ref "U2") (pin "185") (pinfunction "GCK3,_I_185") (pintype "input"))
    )
    (net (code "166") (name "unconnected-(U2A-I{slash}O,_L0P_YY-Pad202)") (class "Default")
      (node (ref "U2") (pin "202") (pinfunction "I/O,_L0P_YY_202") (pintype "bidirectional"))
    )
    (net (code "167") (name "unconnected-(U2A-I{slash}O,_L1P_Y-Pad198)") (class "Default")
      (node (ref "U2") (pin "198") (pinfunction "I/O,_L1P_Y_198") (pintype "bidirectional"))
    )
    (net (code "168") (name "unconnected-(U2A-I{slash}O,_L2N_Y-Pad194)") (class "Default")
      (node (ref "U2") (pin "194") (pinfunction "I/O,_L2N_Y_194") (pintype "bidirectional"))
    )
    (net (code "169") (name "unconnected-(U2A-I{slash}O,_L2P_Y-Pad193)") (class "Default")
      (node (ref "U2") (pin "193") (pinfunction "I/O,_L2P_Y_193") (pintype "bidirectional"))
    )
    (net (code "170") (name "unconnected-(U2A-I{slash}O,_L3N_Y-Pad192)") (class "Default")
      (node (ref "U2") (pin "192") (pinfunction "I/O,_L3N_Y_192") (pintype "bidirectional"))
    )
    (net (code "171") (name "unconnected-(U2A-I{slash}O,_L3P_Y-Pad191)") (class "Default")
      (node (ref "U2") (pin "191") (pinfunction "I/O,_L3P_Y_191") (pintype "bidirectional"))
    )
    (net (code "172") (name "unconnected-(U2A-I{slash}O,_L4P_Y-Pad188)") (class "Default")
      (node (ref "U2") (pin "188") (pinfunction "I/O,_L4P_Y_188") (pintype "bidirectional"))
    )
    (net (code "173") (name "unconnected-(U2A-I{slash}O,_L6N_Y-Pad179)") (class "Default")
      (node (ref "U2") (pin "179") (pinfunction "I/O,_L6N_Y_179") (pintype "bidirectional"))
    )
    (net (code "174") (name "unconnected-(U2A-I{slash}O,_L7N_Y-Pad176)") (class "Default")
      (node (ref "U2") (pin "176") (pinfunction "I/O,_L7N_Y_176") (pintype "bidirectional"))
    )
    (net (code "175") (name "unconnected-(U2A-I{slash}O,_L7P_Y-Pad175)") (class "Default")
      (node (ref "U2") (pin "175") (pinfunction "I/O,_L7P_Y_175") (pintype "bidirectional"))
    )
    (net (code "176") (name "unconnected-(U2A-I{slash}O,_L8N_Y-Pad174)") (class "Default")
      (node (ref "U2") (pin "174") (pinfunction "I/O,_L8N_Y_174") (pintype "bidirectional"))
    )
    (net (code "177") (name "unconnected-(U2A-I{slash}O,_L8P_Y-Pad173)") (class "Default")
      (node (ref "U2") (pin "173") (pinfunction "I/O,_L8P_Y_173") (pintype "bidirectional"))
    )
    (net (code "178") (name "unconnected-(U2A-I{slash}O,_L9N_Y-Pad169)") (class "Default")
      (node (ref "U2") (pin "169") (pinfunction "I/O,_L9N_Y_169") (pintype "bidirectional"))
    )
    (net (code "179") (name "unconnected-(U2A-I{slash}O,_L10N_YY-Pad165)") (class "Default")
      (node (ref "U2") (pin "165") (pinfunction "I/O,_L10N_YY_165") (pintype "bidirectional"))
    )
    (net (code "180") (name "unconnected-(U2A-I{slash}O,_L13P-Pad151)") (class "Default")
      (node (ref "U2") (pin "151") (pinfunction "I/O,_L13P_151") (pintype "bidirectional"))
    )
    (net (code "181") (name "unconnected-(U2A-I{slash}O,_L15N_YY-Pad140)") (class "Default")
      (node (ref "U2") (pin "140") (pinfunction "I/O,_L15N_YY_140") (pintype "bidirectional"))
    )
    (net (code "182") (name "unconnected-(U2A-I{slash}O,_L16N_YY-Pad138)") (class "Default")
      (node (ref "U2") (pin "138") (pinfunction "I/O,_L16N_YY_138") (pintype "bidirectional"))
    )
    (net (code "183") (name "unconnected-(U2A-I{slash}O,_L16P_YY-Pad139)") (class "Default")
      (node (ref "U2") (pin "139") (pinfunction "I/O,_L16P_YY_139") (pintype "bidirectional"))
    )
    (net (code "184") (name "unconnected-(U2A-I{slash}O,_L18P_YY-Pad133)") (class "Default")
      (node (ref "U2") (pin "133") (pinfunction "I/O,_L18P_YY_133") (pintype "bidirectional"))
    )
    (net (code "185") (name "unconnected-(U2A-I{slash}O,_L20N_YY-Pad122)") (class "Default")
      (node (ref "U2") (pin "122") (pinfunction "I/O,_L20N_YY_122") (pintype "bidirectional"))
    )
    (net (code "186") (name "unconnected-(U2A-I{slash}O,_L20P_YY-Pad123)") (class "Default")
      (node (ref "U2") (pin "123") (pinfunction "I/O,_L20P_YY_123") (pintype "bidirectional"))
    )
    (net (code "187") (name "unconnected-(U2A-I{slash}O,_L21P_YY-Pad121)") (class "Default")
      (node (ref "U2") (pin "121") (pinfunction "I/O,_L21P_YY_121") (pintype "bidirectional"))
    )
    (net (code "188") (name "unconnected-(U2A-I{slash}O,_L23P_Y-Pad112)") (class "Default")
      (node (ref "U2") (pin "112") (pinfunction "I/O,_L23P_Y_112") (pintype "bidirectional"))
    )
    (net (code "189") (name "unconnected-(U2A-I{slash}O,_L25N_YY-Pad101)") (class "Default")
      (node (ref "U2") (pin "101") (pinfunction "I/O,_L25N_YY_101") (pintype "bidirectional"))
    )
    (net (code "190") (name "unconnected-(U2A-I{slash}O,_L25P_YY-Pad102)") (class "Default")
      (node (ref "U2") (pin "102") (pinfunction "I/O,_L25P_YY_102") (pintype "bidirectional"))
    )
    (net (code "191") (name "unconnected-(U2A-I{slash}O,_L26N_YY-Pad97)") (class "Default")
      (node (ref "U2") (pin "97") (pinfunction "I/O,_L26N_YY_97") (pintype "bidirectional"))
    )
    (net (code "192") (name "unconnected-(U2A-I{slash}O,_L27N_Y-Pad93)") (class "Default")
      (node (ref "U2") (pin "93") (pinfunction "I/O,_L27N_Y_93") (pintype "bidirectional"))
    )
    (net (code "193") (name "unconnected-(U2A-I{slash}O,_L28N_Y-Pad88)") (class "Default")
      (node (ref "U2") (pin "88") (pinfunction "I/O,_L28N_Y_88") (pintype "bidirectional"))
    )
    (net (code "194") (name "unconnected-(U2A-I{slash}O,_L28P_Y-Pad89)") (class "Default")
      (node (ref "U2") (pin "89") (pinfunction "I/O,_L28P_Y_89") (pintype "bidirectional"))
    )
    (net (code "195") (name "unconnected-(U2A-I{slash}O,_L29N_Y-Pad86)") (class "Default")
      (node (ref "U2") (pin "86") (pinfunction "I/O,_L29N_Y_86") (pintype "bidirectional"))
    )
    (net (code "196") (name "unconnected-(U2A-I{slash}O,_L29P_Y-Pad87)") (class "Default")
      (node (ref "U2") (pin "87") (pinfunction "I/O,_L29P_Y_87") (pintype "bidirectional"))
    )
    (net (code "197") (name "unconnected-(U2A-I{slash}O,_L30N_Y-Pad83)") (class "Default")
      (node (ref "U2") (pin "83") (pinfunction "I/O,_L30N_Y_83") (pintype "bidirectional"))
    )
    (net (code "198") (name "unconnected-(U2A-I{slash}O,_L32N-Pad71)") (class "Default")
      (node (ref "U2") (pin "71") (pinfunction "I/O,_L32N_71") (pintype "bidirectional"))
    )
    (net (code "199") (name "unconnected-(U2A-I{slash}O,_L33N_Y-Pad68)") (class "Default")
      (node (ref "U2") (pin "68") (pinfunction "I/O,_L33N_Y_68") (pintype "bidirectional"))
    )
    (net (code "200") (name "unconnected-(U2A-I{slash}O,_L33P_Y-Pad69)") (class "Default")
      (node (ref "U2") (pin "69") (pinfunction "I/O,_L33P_Y_69") (pintype "bidirectional"))
    )
    (net (code "201") (name "unconnected-(U2A-I{slash}O,_L34P_Y-Pad64)") (class "Default")
      (node (ref "U2") (pin "64") (pinfunction "I/O,_L34P_Y_64") (pintype "bidirectional"))
    )
    (net (code "202") (name "unconnected-(U2A-I{slash}O,_L35N-Pad61)") (class "Default")
      (node (ref "U2") (pin "61") (pinfunction "I/O,_L35N_61") (pintype "bidirectional"))
    )
    (net (code "203") (name "unconnected-(U2A-I{slash}O,_L35P-Pad62)") (class "Default")
      (node (ref "U2") (pin "62") (pinfunction "I/O,_L35P_62") (pintype "bidirectional"))
    )
    (net (code "204") (name "unconnected-(U2A-I{slash}O,_L36P_YY-Pad60)") (class "Default")
      (node (ref "U2") (pin "60") (pinfunction "I/O,_L36P_YY_60") (pintype "bidirectional"))
    )
    (net (code "205") (name "unconnected-(U2A-I{slash}O,_L37N_YY-Pad55)") (class "Default")
      (node (ref "U2") (pin "55") (pinfunction "I/O,_L37N_YY_55") (pintype "bidirectional"))
    )
    (net (code "206") (name "unconnected-(U2A-I{slash}O,_L37P_YY-Pad56)") (class "Default")
      (node (ref "U2") (pin "56") (pinfunction "I/O,_L37P_YY_56") (pintype "bidirectional"))
    )
    (net (code "207") (name "unconnected-(U2A-I{slash}O,_L38N_YY-Pad49)") (class "Default")
      (node (ref "U2") (pin "49") (pinfunction "I/O,_L38N_YY_49") (pintype "bidirectional"))
    )
    (net (code "208") (name "unconnected-(U2A-I{slash}O,_L38P_YY-Pad48)") (class "Default")
      (node (ref "U2") (pin "48") (pinfunction "I/O,_L38P_YY_48") (pintype "bidirectional"))
    )
    (net (code "209") (name "unconnected-(U2A-I{slash}O,_L39N-Pad46)") (class "Default")
      (node (ref "U2") (pin "46") (pinfunction "I/O,_L39N_46") (pintype "bidirectional"))
    )
    (net (code "210") (name "unconnected-(U2A-I{slash}O,_L40P-Pad40)") (class "Default")
      (node (ref "U2") (pin "40") (pinfunction "I/O,_L40P_40") (pintype "bidirectional"))
    )
    (net (code "211") (name "unconnected-(U2A-I{slash}O,_L41N_YY-Pad36)") (class "Default")
      (node (ref "U2") (pin "36") (pinfunction "I/O,_L41N_YY_36") (pintype "bidirectional"))
    )
    (net (code "212") (name "unconnected-(U2A-I{slash}O,_L41P_YY-Pad35)") (class "Default")
      (node (ref "U2") (pin "35") (pinfunction "I/O,_L41P_YY_35") (pintype "bidirectional"))
    )
    (net (code "213") (name "unconnected-(U2A-I{slash}O,_L43P-Pad30)") (class "Default")
      (node (ref "U2") (pin "30") (pinfunction "I/O,_L43P_30") (pintype "bidirectional"))
    )
    (net (code "214") (name "unconnected-(U2A-I{slash}O,_L46P_YY-Pad17)") (class "Default")
      (node (ref "U2") (pin "17") (pinfunction "I/O,_L46P_YY_17") (pintype "bidirectional"))
    )
    (net (code "215") (name "unconnected-(U2A-I{slash}O,_L47N_YY-Pad16)") (class "Default")
      (node (ref "U2") (pin "16") (pinfunction "I/O,_L47N_YY_16") (pintype "bidirectional"))
    )
    (net (code "216") (name "unconnected-(U2A-I{slash}O,_L47P_YY-Pad15)") (class "Default")
      (node (ref "U2") (pin "15") (pinfunction "I/O,_L47P_YY_15") (pintype "bidirectional"))
    )
    (net (code "217") (name "unconnected-(U2A-I{slash}O,_L48N-Pad11)") (class "Default")
      (node (ref "U2") (pin "11") (pinfunction "I/O,_L48N_11") (pintype "bidirectional"))
    )
    (net (code "218") (name "unconnected-(U2A-I{slash}O,_L49N_Y-Pad7)") (class "Default")
      (node (ref "U2") (pin "7") (pinfunction "I/O,_L49N_Y_7") (pintype "bidirectional"))
    )
    (net (code "219") (name "unconnected-(U2A-I{slash}O,_VREF_0,_L0N_YY-Pad203)") (class "Default")
      (node (ref "U2") (pin "203") (pinfunction "I/O,_VREF_0,_L0N_YY_203") (pintype "bidirectional"))
    )
    (net (code "220") (name "unconnected-(U2A-I{slash}O,_VREF_0,_L1N_Y-Pad199)") (class "Default")
      (node (ref "U2") (pin "199") (pinfunction "I/O,_VREF_0,_L1N_Y_199") (pintype "bidirectional"))
    )
    (net (code "221") (name "unconnected-(U2A-I{slash}O,_VREF_0,_L4N_Y-Pad189)") (class "Default")
      (node (ref "U2") (pin "189") (pinfunction "I/O,_VREF_0,_L4N_Y_189") (pintype "bidirectional"))
    )
    (net (code "222") (name "unconnected-(U2A-I{slash}O,_VREF_0-Pad205)") (class "Default")
      (node (ref "U2") (pin "205") (pinfunction "I/O,_VREF_0_205") (pintype "bidirectional"))
    )
    (net (code "223") (name "unconnected-(U2A-I{slash}O,_VREF_1,_L6P_Y-Pad178)") (class "Default")
      (node (ref "U2") (pin "178") (pinfunction "I/O,_VREF_1,_L6P_Y_178") (pintype "bidirectional"))
    )
    (net (code "224") (name "unconnected-(U2A-I{slash}O,_VREF_1,_L9P_Y-Pad168)") (class "Default")
      (node (ref "U2") (pin "168") (pinfunction "I/O,_VREF_1,_L9P_Y_168") (pintype "bidirectional"))
    )
    (net (code "225") (name "unconnected-(U2A-I{slash}O,_VREF_1,_L10P_YY-Pad164)") (class "Default")
      (node (ref "U2") (pin "164") (pinfunction "I/O,_VREF_1,_L10P_YY_164") (pintype "bidirectional"))
    )
    (net (code "226") (name "unconnected-(U2A-I{slash}O,_VREF_1-Pad162)") (class "Default")
      (node (ref "U2") (pin "162") (pinfunction "I/O,_VREF_1_162") (pintype "bidirectional"))
    )
    (net (code "227") (name "unconnected-(U2A-I{slash}O,_VREF_2,_L13N-Pad150)") (class "Default")
      (node (ref "U2") (pin "150") (pinfunction "I/O,_VREF_2,_L13N_150") (pintype "bidirectional"))
    )
    (net (code "228") (name "unconnected-(U2A-I{slash}O,_VREF_2,_L14P-Pad146)") (class "Default")
      (node (ref "U2") (pin "146") (pinfunction "I/O,_VREF_2,_L14P_146") (pintype "bidirectional"))
    )
    (net (code "229") (name "unconnected-(U2A-I{slash}O,_VREF_2,_L17P-Pad136)") (class "Default")
      (node (ref "U2") (pin "136") (pinfunction "I/O,_VREF_2,_L17P_136") (pintype "bidirectional"))
    )
    (net (code "230") (name "unconnected-(U2A-I{slash}O,_VREF_2-Pad152)") (class "Default")
      (node (ref "U2") (pin "152") (pinfunction "I/O,_VREF_2_152") (pintype "bidirectional"))
    )
    (net (code "231") (name "unconnected-(U2A-I{slash}O,_VREF_3,_L19N-Pad125)") (class "Default")
      (node (ref "U2") (pin "125") (pinfunction "I/O,_VREF_3,_L19N_125") (pintype "bidirectional"))
    )
    (net (code "232") (name "unconnected-(U2A-I{slash}O,_VREF_3,_L22N-Pad115)") (class "Default")
      (node (ref "U2") (pin "115") (pinfunction "I/O,_VREF_3,_L22N_115") (pintype "bidirectional"))
    )
    (net (code "233") (name "unconnected-(U2A-I{slash}O,_VREF_3,_L23N_Y-Pad111)") (class "Default")
      (node (ref "U2") (pin "111") (pinfunction "I/O,_VREF_3,_L23N_Y_111") (pintype "bidirectional"))
    )
    (net (code "234") (name "unconnected-(U2A-I{slash}O,_VREF_3-Pad109)") (class "Default")
      (node (ref "U2") (pin "109") (pinfunction "I/O,_VREF_3_109") (pintype "bidirectional"))
    )
    (net (code "235") (name "unconnected-(U2A-I{slash}O,_VREF_4,_L26P_YY-Pad98)") (class "Default")
      (node (ref "U2") (pin "98") (pinfunction "I/O,_VREF_4,_L26P_YY_98") (pintype "bidirectional"))
    )
    (net (code "236") (name "unconnected-(U2A-I{slash}O,_VREF_4,_L27P_Y-Pad94)") (class "Default")
      (node (ref "U2") (pin "94") (pinfunction "I/O,_VREF_4,_L27P_Y_94") (pintype "bidirectional"))
    )
    (net (code "237") (name "unconnected-(U2A-I{slash}O,_VREF_4,_L30P_Y-Pad84)") (class "Default")
      (node (ref "U2") (pin "84") (pinfunction "I/O,_VREF_4,_L30P_Y_84") (pintype "bidirectional"))
    )
    (net (code "238") (name "unconnected-(U2A-I{slash}O,_VREF_4-Pad100)") (class "Default")
      (node (ref "U2") (pin "100") (pinfunction "I/O,_VREF_4_100") (pintype "bidirectional"))
    )
    (net (code "239") (name "unconnected-(U2A-I{slash}O,_VREF_5,_L32P-Pad73)") (class "Default")
      (node (ref "U2") (pin "73") (pinfunction "I/O,_VREF_5,_L32P_73") (pintype "bidirectional"))
    )
    (net (code "240") (name "unconnected-(U2A-I{slash}O,_VREF_5,_L34N_Y-Pad63)") (class "Default")
      (node (ref "U2") (pin "63") (pinfunction "I/O,_VREF_5,_L34N_Y_63") (pintype "bidirectional"))
    )
    (net (code "241") (name "unconnected-(U2A-I{slash}O,_VREF_5,_L36N_YY-Pad59)") (class "Default")
      (node (ref "U2") (pin "59") (pinfunction "I/O,_VREF_5,_L36N_YY_59") (pintype "bidirectional"))
    )
    (net (code "242") (name "unconnected-(U2A-I{slash}O,_VREF_5-Pad57)") (class "Default")
      (node (ref "U2") (pin "57") (pinfunction "I/O,_VREF_5_57") (pintype "bidirectional"))
    )
    (net (code "243") (name "unconnected-(U2A-I{slash}O,_VREF_6,_L39P-Pad45)") (class "Default")
      (node (ref "U2") (pin "45") (pinfunction "I/O,_VREF_6,_L39P_45") (pintype "bidirectional"))
    )
    (net (code "244") (name "unconnected-(U2A-I{slash}O,_VREF_6,_L40N-Pad41)") (class "Default")
      (node (ref "U2") (pin "41") (pinfunction "I/O,_VREF_6,_L40N_41") (pintype "bidirectional"))
    )
    (net (code "245") (name "unconnected-(U2A-I{slash}O,_VREF_6,_L43N-Pad31)") (class "Default")
      (node (ref "U2") (pin "31") (pinfunction "I/O,_VREF_6,_L43N_31") (pintype "bidirectional"))
    )
    (net (code "246") (name "unconnected-(U2A-I{slash}O,_VREF_6-Pad47)") (class "Default")
      (node (ref "U2") (pin "47") (pinfunction "I/O,_VREF_6_47") (pintype "bidirectional"))
    )
    (net (code "247") (name "unconnected-(U2A-I{slash}O,_VREF_7,_L48P-Pad10)") (class "Default")
      (node (ref "U2") (pin "10") (pinfunction "I/O,_VREF_7,_L48P_10") (pintype "bidirectional"))
    )
    (net (code "248") (name "unconnected-(U2A-I{slash}O,_VREF_7,_L49P_Y-Pad6)") (class "Default")
      (node (ref "U2") (pin "6") (pinfunction "I/O,_VREF_7,_L49P_Y_6") (pintype "bidirectional"))
    )
    (net (code "249") (name "unconnected-(U2A-I{slash}O,_VREF_7-Pad4)") (class "Default")
      (node (ref "U2") (pin "4") (pinfunction "I/O,_VREF_7_4") (pintype "bidirectional"))
    )
    (net (code "250") (name "unconnected-(U2A-I{slash}O-Pad3)") (class "Default")
      (node (ref "U2") (pin "3") (pinfunction "I/O_3") (pintype "bidirectional"))
    )
    (net (code "251") (name "unconnected-(U2A-I{slash}O-Pad5)") (class "Default")
      (node (ref "U2") (pin "5") (pinfunction "I/O_5") (pintype "bidirectional"))
    )
    (net (code "252") (name "unconnected-(U2A-I{slash}O-Pad8)") (class "Default")
      (node (ref "U2") (pin "8") (pinfunction "I/O_8") (pintype "bidirectional"))
    )
    (net (code "253") (name "unconnected-(U2A-I{slash}O-Pad9)") (class "Default")
      (node (ref "U2") (pin "9") (pinfunction "I/O_9") (pintype "bidirectional"))
    )
    (net (code "254") (name "unconnected-(U2A-I{slash}O-Pad29)") (class "Default")
      (node (ref "U2") (pin "29") (pinfunction "I/O_29") (pintype "bidirectional"))
    )
    (net (code "255") (name "unconnected-(U2A-I{slash}O-Pad42)") (class "Default")
      (node (ref "U2") (pin "42") (pinfunction "I/O_42") (pintype "bidirectional"))
    )
    (net (code "256") (name "unconnected-(U2A-I{slash}O-Pad43)") (class "Default")
      (node (ref "U2") (pin "43") (pinfunction "I/O_43") (pintype "bidirectional"))
    )
    (net (code "257") (name "unconnected-(U2A-I{slash}O-Pad44)") (class "Default")
      (node (ref "U2") (pin "44") (pinfunction "I/O_44") (pintype "bidirectional"))
    )
    (net (code "258") (name "unconnected-(U2A-I{slash}O-Pad58)") (class "Default")
      (node (ref "U2") (pin "58") (pinfunction "I/O_58") (pintype "bidirectional"))
    )
    (net (code "259") (name "unconnected-(U2A-I{slash}O-Pad70)") (class "Default")
      (node (ref "U2") (pin "70") (pinfunction "I/O_70") (pintype "bidirectional"))
    )
    (net (code "260") (name "unconnected-(U2A-I{slash}O-Pad74)") (class "Default")
      (node (ref "U2") (pin "74") (pinfunction "I/O_74") (pintype "bidirectional"))
    )
    (net (code "261") (name "unconnected-(U2A-I{slash}O-Pad82)") (class "Default")
      (node (ref "U2") (pin "82") (pinfunction "I/O_82") (pintype "bidirectional"))
    )
    (net (code "262") (name "unconnected-(U2A-I{slash}O-Pad95)") (class "Default")
      (node (ref "U2") (pin "95") (pinfunction "I/O_95") (pintype "bidirectional"))
    )
    (net (code "263") (name "unconnected-(U2A-I{slash}O-Pad96)") (class "Default")
      (node (ref "U2") (pin "96") (pinfunction "I/O_96") (pintype "bidirectional"))
    )
    (net (code "264") (name "unconnected-(U2A-I{slash}O-Pad99)") (class "Default")
      (node (ref "U2") (pin "99") (pinfunction "I/O_99") (pintype "bidirectional"))
    )
    (net (code "265") (name "unconnected-(U2A-I{slash}O-Pad110)") (class "Default")
      (node (ref "U2") (pin "110") (pinfunction "I/O_110") (pintype "bidirectional"))
    )
    (net (code "266") (name "unconnected-(U2A-I{slash}O-Pad113)") (class "Default")
      (node (ref "U2") (pin "113") (pinfunction "I/O_113") (pintype "bidirectional"))
    )
    (net (code "267") (name "unconnected-(U2A-I{slash}O-Pad114)") (class "Default")
      (node (ref "U2") (pin "114") (pinfunction "I/O_114") (pintype "bidirectional"))
    )
    (net (code "268") (name "unconnected-(U2A-I{slash}O-Pad127)") (class "Default")
      (node (ref "U2") (pin "127") (pinfunction "I/O_127") (pintype "bidirectional"))
    )
    (net (code "269") (name "unconnected-(U2A-I{slash}O-Pad134)") (class "Default")
      (node (ref "U2") (pin "134") (pinfunction "I/O_134") (pintype "bidirectional"))
    )
    (net (code "270") (name "unconnected-(U2A-I{slash}O-Pad147)") (class "Default")
      (node (ref "U2") (pin "147") (pinfunction "I/O_147") (pintype "bidirectional"))
    )
    (net (code "271") (name "unconnected-(U2A-I{slash}O-Pad148)") (class "Default")
      (node (ref "U2") (pin "148") (pinfunction "I/O_148") (pintype "bidirectional"))
    )
    (net (code "272") (name "unconnected-(U2A-I{slash}O-Pad149)") (class "Default")
      (node (ref "U2") (pin "149") (pinfunction "I/O_149") (pintype "bidirectional"))
    )
    (net (code "273") (name "unconnected-(U2A-I{slash}O-Pad163)") (class "Default")
      (node (ref "U2") (pin "163") (pinfunction "I/O_163") (pintype "bidirectional"))
    )
    (net (code "274") (name "unconnected-(U2A-I{slash}O-Pad166)") (class "Default")
      (node (ref "U2") (pin "166") (pinfunction "I/O_166") (pintype "bidirectional"))
    )
    (net (code "275") (name "unconnected-(U2A-I{slash}O-Pad167)") (class "Default")
      (node (ref "U2") (pin "167") (pinfunction "I/O_167") (pintype "bidirectional"))
    )
    (net (code "276") (name "unconnected-(U2A-I{slash}O-Pad180)") (class "Default")
      (node (ref "U2") (pin "180") (pinfunction "I/O_180") (pintype "bidirectional"))
    )
    (net (code "277") (name "unconnected-(U2A-I{slash}O-Pad200)") (class "Default")
      (node (ref "U2") (pin "200") (pinfunction "I/O_200") (pintype "bidirectional"))
    )
    (net (code "278") (name "unconnected-(U2A-I{slash}O-Pad201)") (class "Default")
      (node (ref "U2") (pin "201") (pinfunction "I/O_201") (pintype "bidirectional"))
    )
    (net (code "279") (name "unconnected-(U2A-I{slash}O-Pad204)") (class "Default")
      (node (ref "U2") (pin "204") (pinfunction "I/O_204") (pintype "bidirectional"))
    )
    (net (code "280") (name "unconnected-(U2A-I{slash}O-Pad206)") (class "Default")
      (node (ref "U2") (pin "206") (pinfunction "I/O_206") (pintype "bidirectional"))
    )
    (net (code "281") (name "unconnected-(U2A-I{slash}O_(D1),_L14N-Pad145)") (class "Default")
      (node (ref "U2") (pin "145") (pinfunction "I/O_(D1),_L14N_145") (pintype "bidirectional"))
    )
    (net (code "282") (name "unconnected-(U2A-I{slash}O_(D2),_L15P_YY-Pad141)") (class "Default")
      (node (ref "U2") (pin "141") (pinfunction "I/O_(D2),_L15P_YY_141") (pintype "bidirectional"))
    )
    (net (code "283") (name "unconnected-(U2A-I{slash}O_(D3),_L17N-Pad135)") (class "Default")
      (node (ref "U2") (pin "135") (pinfunction "I/O_(D3),_L17N_135") (pintype "bidirectional"))
    )
    (net (code "284") (name "unconnected-(U2A-I{slash}O_(D4),_L19P-Pad126)") (class "Default")
      (node (ref "U2") (pin "126") (pinfunction "I/O_(D4),_L19P_126") (pintype "bidirectional"))
    )
    (net (code "285") (name "unconnected-(U2A-I{slash}O_(D5),_L21N_YY-Pad120)") (class "Default")
      (node (ref "U2") (pin "120") (pinfunction "I/O_(D5),_L21N_YY_120") (pintype "bidirectional"))
    )
    (net (code "286") (name "unconnected-(U2A-I{slash}O_(D6),_L22P-Pad116)") (class "Default")
      (node (ref "U2") (pin "116") (pinfunction "I/O_(D6),_L22P_116") (pintype "bidirectional"))
    )
    (net (code "287") (name "unconnected-(U2A-I{slash}O_(D7),_L24P_YY-Pad108)") (class "Default")
      (node (ref "U2") (pin "108") (pinfunction "I/O_(D7),_L24P_YY_108") (pintype "bidirectional"))
    )
    (net (code "288") (name "unconnected-(U2A-I{slash}O_(DLL),_L5N-Pad187)") (class "Default")
      (node (ref "U2") (pin "187") (pinfunction "I/O_(DLL),_L5N_187") (pintype "bidirectional"))
    )
    (net (code "289") (name "unconnected-(U2A-I{slash}O_(DLL),_L5P-Pad181)") (class "Default")
      (node (ref "U2") (pin "181") (pinfunction "I/O_(DLL),_L5P_181") (pintype "bidirectional"))
    )
    (net (code "290") (name "unconnected-(U2A-I{slash}O_(DLL),_L31N-Pad75)") (class "Default")
      (node (ref "U2") (pin "75") (pinfunction "I/O_(DLL),_L31N_75") (pintype "bidirectional"))
    )
    (net (code "291") (name "unconnected-(U2A-I{slash}O_(DLL),_L31P-Pad81)") (class "Default")
      (node (ref "U2") (pin "81") (pinfunction "I/O_(DLL),_L31P_81") (pintype "bidirectional"))
    )
    (net (code "292") (name "unconnected-(U2A-I{slash}O_(DOUT,_BUSY),_L12P_YY-Pad154)") (class "Default")
      (node (ref "U2") (pin "154") (pinfunction "I/O_(DOUT,_BUSY),_L12P_YY_154") (pintype "bidirectional"))
    )
    (net (code "293") (name "unconnected-(U2A-I{slash}O_(IRDY),_L18N_YY-Pad132)") (class "Default")
      (node (ref "U2") (pin "132") (pinfunction "I/O_(IRDY),_L18N_YY_132") (pintype "bidirectional"))
    )
    (net (code "294") (name "unconnected-(U2A-I{slash}O_(TRDY)-Pad27)") (class "Default")
      (node (ref "U2") (pin "27") (pinfunction "I/O_(TRDY)_27") (pintype "bidirectional"))
    )
    (net (code "295") (name "unconnected-(U2A-I{slash}O_(TRDY)-Pad129)") (class "Default")
      (node (ref "U2") (pin "129") (pinfunction "I/O_(TRDY)_129") (pintype "bidirectional"))
    )
    (net (code "296") (name "unconnected-(U2A-I{slash}O_(~{CS}),_L11P_YY-Pad160)") (class "Default")
      (node (ref "U2") (pin "160") (pinfunction "I/O_(~{CS}),_L11P_YY_160") (pintype "bidirectional"))
    )
    (net (code "297") (name "unconnected-(U2A-I{slash}O_(~{WRITE}),_L11N_YY-Pad161)") (class "Default")
      (node (ref "U2") (pin "161") (pinfunction "I/O_(~{WRITE}),_L11N_YY_161") (pintype "bidirectional"))
    )
    (net (code "298") (name "unconnected-(U2B-CCLK-Pad155)") (class "Default")
      (node (ref "U2") (pin "155") (pinfunction "CCLK_155") (pintype "bidirectional"))
    )
    (net (code "299") (name "unconnected-(U2B-DIN-Pad153)") (class "Default")
      (node (ref "U2") (pin "153") (pinfunction "DIN_153") (pintype "bidirectional"))
    )
    (net (code "300") (name "unconnected-(U2B-DONE-Pad104)") (class "Default")
      (node (ref "U2") (pin "104") (pinfunction "DONE_104") (pintype "bidirectional"))
    )
    (net (code "301") (name "unconnected-(U2B-M0-Pad52)") (class "Default")
      (node (ref "U2") (pin "52") (pinfunction "M0_52") (pintype "input"))
    )
    (net (code "302") (name "unconnected-(U2B-M1-Pad50)") (class "Default")
      (node (ref "U2") (pin "50") (pinfunction "M1_50") (pintype "input"))
    )
    (net (code "303") (name "unconnected-(U2B-M2-Pad54)") (class "Default")
      (node (ref "U2") (pin "54") (pinfunction "M2_54") (pintype "input"))
    )
    (net (code "304") (name "unconnected-(U2B-PROGRAM-Pad106)") (class "Default")
      (node (ref "U2") (pin "106") (pinfunction "PROGRAM_106") (pintype "input"))
    )
    (net (code "305") (name "unconnected-(U2B-TCK-Pad207)") (class "Default")
      (node (ref "U2") (pin "207") (pinfunction "TCK_207") (pintype "input"))
    )
    (net (code "306") (name "unconnected-(U2B-TDI-Pad159)") (class "Default")
      (node (ref "U2") (pin "159") (pinfunction "TDI_159") (pintype "input"))
    )
    (net (code "307") (name "unconnected-(U2B-TDO-Pad157)") (class "Default")
      (node (ref "U2") (pin "157") (pinfunction "TDO_157") (pintype "output"))
    )
    (net (code "308") (name "unconnected-(U2B-TMS-Pad2)") (class "Default")
      (node (ref "U2") (pin "2") (pinfunction "TMS_2") (pintype "input"))
    )
    (net (code "309") (name "unconnected-(U2B-~{INIT}-Pad107)") (class "Default")
      (node (ref "U2") (pin "107") (pinfunction "~{INIT}_107") (pintype "bidirectional"))
    )
  )
)
